# butter.net
KiCad netlist of a schematic drawn in EAGLE
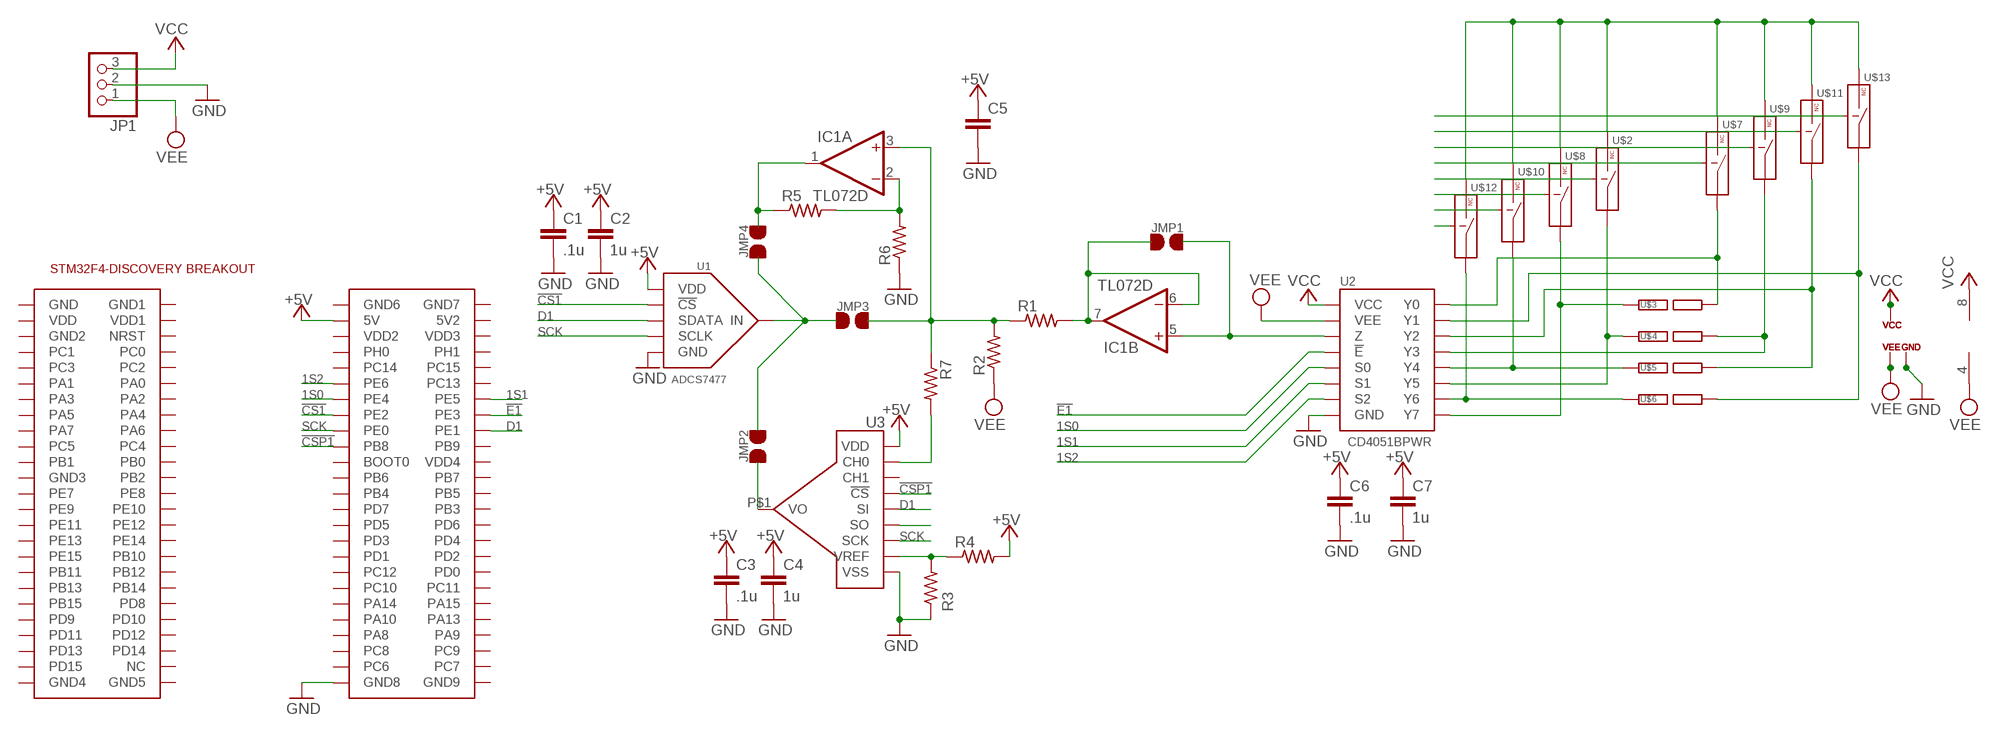
[diagram p0: schematic, sheet 1]

(export (version "E")
  (design (tool "Eeschema 10.0.6"))
  (components
    (comp (ref "C1")
      (value ".1u")
      (footprint "eagle-import:C0805")
      (libsource (lib "eagle-import") (part "C-EUC0805"))
    )
    (comp (ref "C2")
      (value "1u")
      (footprint "eagle-import:C0805")
      (libsource (lib "eagle-import") (part "C-EUC0805"))
    )
    (comp (ref "C3")
      (value ".1u")
      (footprint "eagle-import:C0805")
      (libsource (lib "eagle-import") (part "C-EUC0805"))
    )
    (comp (ref "C4")
      (value "1u")
      (footprint "eagle-import:C0805")
      (libsource (lib "eagle-import") (part "C-EUC0805"))
    )
    (comp (ref "C5")
      (value "C-EUC0805")
      (footprint "eagle-import:C0805")
      (libsource (lib "eagle-import") (part "C-EUC0805"))
    )
    (comp (ref "C6")
      (value ".1u")
      (footprint "eagle-import:C0805")
      (libsource (lib "eagle-import") (part "C-EUC0805"))
    )
    (comp (ref "C7")
      (value "1u")
      (footprint "eagle-import:C0805")
      (libsource (lib "eagle-import") (part "C-EUC0805"))
    )
    (comp (ref "IC1")
      (value "TL072D")
      (footprint "eagle-import:SO08")
      (libsource (lib "eagle-import") (part "TL072D"))
    )
    (comp (ref "JMP1")
      (value "JMP")
      (footprint "eagle-import:JMP")
      (libsource (lib "eagle-import") (part "JMP"))
    )
    (comp (ref "JMP2")
      (value "JMP")
      (footprint "eagle-import:JMP")
      (libsource (lib "eagle-import") (part "JMP"))
    )
    (comp (ref "JMP3")
      (value "JMP")
      (footprint "eagle-import:JMP")
      (libsource (lib "eagle-import") (part "JMP"))
    )
    (comp (ref "JMP4")
      (value "JMP")
      (footprint "eagle-import:JMP")
      (libsource (lib "eagle-import") (part "JMP"))
    )
    (comp (ref "JP1")
      (value "PINHD-1X3")
      (footprint "eagle-import:1X03")
      (libsource (lib "eagle-import") (part "PINHD-1X3"))
    )
    (comp (ref "R1")
      (value "R-US_R0603")
      (footprint "eagle-import:R0603")
      (libsource (lib "eagle-import") (part "R-US_R0603"))
    )
    (comp (ref "R2")
      (value "R-US_R0603")
      (footprint "eagle-import:R0603")
      (libsource (lib "eagle-import") (part "R-US_R0603"))
    )
    (comp (ref "R3")
      (value "R-US_R0603")
      (footprint "eagle-import:R0603")
      (libsource (lib "eagle-import") (part "R-US_R0603"))
    )
    (comp (ref "R4")
      (value "R-US_R0603")
      (footprint "eagle-import:R0603")
      (libsource (lib "eagle-import") (part "R-US_R0603"))
    )
    (comp (ref "R5")
      (value "R-US_R0603")
      (footprint "eagle-import:R0603")
      (libsource (lib "eagle-import") (part "R-US_R0603"))
    )
    (comp (ref "R6")
      (value "R-US_R0603")
      (footprint "eagle-import:R0603")
      (libsource (lib "eagle-import") (part "R-US_R0603"))
    )
    (comp (ref "R7")
      (value "R-US_R0603")
      (footprint "eagle-import:R0603")
      (libsource (lib "eagle-import") (part "R-US_R0603"))
    )
    (comp (ref "U$1")
      (value "STM32F4-DISCOVERY")
      (footprint "eagle-import:STM32F4-DISCOVERY")
      (libsource (lib "eagle-import") (part "STM32F4-DISCOVERY"))
    )
    (comp (ref "U$2")
      (value "DG467")
      (footprint "eagle-import:TSSOP-6")
      (libsource (lib "eagle-import") (part "DG467"))
    )
    (comp (ref "U$3")
      (value "RAILSEP")
      (footprint "eagle-import:RAIL")
      (libsource (lib "eagle-import") (part "RAILSEP"))
    )
    (comp (ref "U$4")
      (value "RAILSEP")
      (footprint "eagle-import:RAIL")
      (libsource (lib "eagle-import") (part "RAILSEP"))
    )
    (comp (ref "U$5")
      (value "RAILSEP")
      (footprint "eagle-import:RAIL")
      (libsource (lib "eagle-import") (part "RAILSEP"))
    )
    (comp (ref "U$6")
      (value "RAILSEP")
      (footprint "eagle-import:RAIL")
      (libsource (lib "eagle-import") (part "RAILSEP"))
    )
    (comp (ref "U$7")
      (value "DG467")
      (footprint "eagle-import:TSSOP-6")
      (libsource (lib "eagle-import") (part "DG467"))
    )
    (comp (ref "U$8")
      (value "DG467")
      (footprint "eagle-import:TSSOP-6")
      (libsource (lib "eagle-import") (part "DG467"))
    )
    (comp (ref "U$9")
      (value "DG467")
      (footprint "eagle-import:TSSOP-6")
      (libsource (lib "eagle-import") (part "DG467"))
    )
    (comp (ref "U$10")
      (value "DG467")
      (footprint "eagle-import:TSSOP-6")
      (libsource (lib "eagle-import") (part "DG467"))
    )
    (comp (ref "U$11")
      (value "DG467")
      (footprint "eagle-import:TSSOP-6")
      (libsource (lib "eagle-import") (part "DG467"))
    )
    (comp (ref "U$12")
      (value "DG467")
      (footprint "eagle-import:TSSOP-6")
      (libsource (lib "eagle-import") (part "DG467"))
    )
    (comp (ref "U$13")
      (value "DG467")
      (footprint "eagle-import:TSSOP-6")
      (libsource (lib "eagle-import") (part "DG467"))
    )
    (comp (ref "U1")
      (value "ADCS7477")
      (footprint "eagle-import:SOT-23-6")
      (libsource (lib "eagle-import") (part "ADCS7477"))
    )
    (comp (ref "U2")
      (value "CD4051BPWR")
      (footprint "eagle-import:TSSOP-16")
      (libsource (lib "eagle-import") (part "CD4051BPWR"))
    )
    (comp (ref "U3")
      (value "MCP6S93")
      (footprint "eagle-import:MSOP-10")
      (libsource (lib "eagle-import") (part "MCP6S93"))
    )
  )
  (nets
    (net (code "1") (name "+5V") (class "Default")
      (node (ref "C1") (pin "1") (pinfunction "1_1") (pintype "passive"))
      (node (ref "C2") (pin "1") (pinfunction "1_1") (pintype "passive"))
      (node (ref "C3") (pin "1") (pinfunction "1_1") (pintype "passive"))
      (node (ref "C4") (pin "1") (pinfunction "1_1") (pintype "passive"))
      (node (ref "C5") (pin "1") (pinfunction "1_1") (pintype "passive"))
      (node (ref "C6") (pin "1") (pinfunction "1_1") (pintype "passive"))
      (node (ref "C7") (pin "1") (pinfunction "1_1") (pintype "passive"))
      (node (ref "R4") (pin "2") (pinfunction "2_2") (pintype "passive"))
      (node (ref "U$1") (pin "P$53") (pinfunction "5V_P$53") (pintype "bidirectional"))
      (node (ref "U1") (pin "P$1") (pinfunction "VDD_P$1") (pintype "bidirectional"))
      (node (ref "U3") (pin "P$10") (pinfunction "VDD_P$10") (pintype "bidirectional"))
    )
    (net (code "2") (name "/1S0") (class "Default")
      (node (ref "U$1") (pin "P$63") (pinfunction "PE4_P$63") (pintype "bidirectional"))
      (node (ref "U2") (pin "P$11") (pinfunction "S0_P$11") (pintype "bidirectional"))
    )
    (net (code "3") (name "/1S1") (class "Default")
      (node (ref "U$1") (pin "P$64") (pinfunction "PE5_P$64") (pintype "bidirectional"))
      (node (ref "U2") (pin "P$10") (pinfunction "S1_P$10") (pintype "bidirectional"))
    )
    (net (code "4") (name "/1S2") (class "Default")
      (node (ref "U$1") (pin "P$61") (pinfunction "PE6_P$61") (pintype "bidirectional"))
      (node (ref "U2") (pin "P$9") (pinfunction "S2_P$9") (pintype "bidirectional"))
    )
    (net (code "5") (name "/D1") (class "Default")
      (node (ref "U$1") (pin "P$68") (pinfunction "PE1_P$68") (pintype "bidirectional"))
      (node (ref "U1") (pin "P$5") (pinfunction "SDATA_P$5") (pintype "bidirectional"))
      (node (ref "U3") (pin "P$7") (pinfunction "SI_P$7") (pintype "bidirectional"))
    )
    (net (code "6") (name "/SCK") (class "Default")
      (node (ref "U$1") (pin "P$67") (pinfunction "PE0_P$67") (pintype "bidirectional"))
      (node (ref "U1") (pin "P$4") (pinfunction "SCLK_P$4") (pintype "bidirectional"))
      (node (ref "U3") (pin "P$9") (pinfunction "SCK_P$9") (pintype "bidirectional"))
    )
    (net (code "7") (name "/~{CS1}") (class "Default")
      (node (ref "U$1") (pin "P$65") (pinfunction "PE2_P$65") (pintype "bidirectional"))
      (node (ref "U1") (pin "P$6") (pinfunction "~{CS}_P$6") (pintype "bidirectional"))
    )
    (net (code "8") (name "/~{CSP1}") (class "Default")
      (node (ref "U$1") (pin "P$69") (pinfunction "PB8_P$69") (pintype "bidirectional"))
      (node (ref "U3") (pin "P$6") (pinfunction "~{CS}_P$6") (pintype "bidirectional"))
    )
    (net (code "9") (name "/~{E1}") (class "Default")
      (node (ref "U$1") (pin "P$66") (pinfunction "PE3_P$66") (pintype "bidirectional"))
      (node (ref "U2") (pin "P$6") (pinfunction "~{E}_P$6") (pintype "bidirectional"))
    )
    (net (code "10") (name "GND") (class "Default")
      (node (ref "C1") (pin "2") (pinfunction "2_2") (pintype "passive"))
      (node (ref "C2") (pin "2") (pinfunction "2_2") (pintype "passive"))
      (node (ref "C3") (pin "2") (pinfunction "2_2") (pintype "passive"))
      (node (ref "C4") (pin "2") (pinfunction "2_2") (pintype "passive"))
      (node (ref "C5") (pin "2") (pinfunction "2_2") (pintype "passive"))
      (node (ref "C6") (pin "2") (pinfunction "2_2") (pintype "passive"))
      (node (ref "C7") (pin "2") (pinfunction "2_2") (pintype "passive"))
      (node (ref "JP1") (pin "2") (pinfunction "2_2") (pintype "passive"))
      (node (ref "R3") (pin "1") (pinfunction "1_1") (pintype "passive"))
      (node (ref "R6") (pin "1") (pinfunction "1_1") (pintype "passive"))
      (node (ref "U$1") (pin "P$99") (pinfunction "GND8_P$99") (pintype "bidirectional"))
      (node (ref "U$10") (pin "P$4") (pinfunction "GND_P$4") (pintype "bidirectional"))
      (node (ref "U$11") (pin "P$4") (pinfunction "GND_P$4") (pintype "bidirectional"))
      (node (ref "U$12") (pin "P$4") (pinfunction "GND_P$4") (pintype "bidirectional"))
      (node (ref "U$13") (pin "P$4") (pinfunction "GND_P$4") (pintype "bidirectional"))
      (node (ref "U$2") (pin "P$4") (pinfunction "GND_P$4") (pintype "bidirectional"))
      (node (ref "U$7") (pin "P$4") (pinfunction "GND_P$4") (pintype "bidirectional"))
      (node (ref "U$8") (pin "P$4") (pinfunction "GND_P$4") (pintype "bidirectional"))
      (node (ref "U$9") (pin "P$4") (pinfunction "GND_P$4") (pintype "bidirectional"))
      (node (ref "U1") (pin "P$2") (pinfunction "GND_P$2") (pintype "bidirectional"))
      (node (ref "U2") (pin "P$8") (pinfunction "GND_P$8") (pintype "bidirectional"))
      (node (ref "U3") (pin "P$5") (pinfunction "VSS_P$5") (pintype "bidirectional"))
    )
    (net (code "11") (name "Net-(IC1A-+IN)") (class "Default")
      (node (ref "IC1") (pin "3") (pinfunction "+IN_3") (pintype "input"))
      (node (ref "JMP3") (pin "P$2") (pinfunction "P$2_P$2") (pintype "bidirectional"))
      (node (ref "R1") (pin "1") (pinfunction "1_1") (pintype "passive"))
      (node (ref "R2") (pin "2") (pinfunction "2_2") (pintype "passive"))
      (node (ref "R7") (pin "1") (pinfunction "1_1") (pintype "passive"))
    )
    (net (code "12") (name "Net-(IC1A--IN)") (class "Default")
      (node (ref "IC1") (pin "2") (pinfunction "-IN_2") (pintype "input"))
      (node (ref "R5") (pin "2") (pinfunction "2_2") (pintype "passive"))
      (node (ref "R6") (pin "2") (pinfunction "2_2") (pintype "passive"))
    )
    (net (code "13") (name "Net-(IC1A-OUT)") (class "Default")
      (node (ref "IC1") (pin "1") (pinfunction "OUT_1") (pintype "output"))
      (node (ref "JMP4") (pin "P$2") (pinfunction "P$2_P$2") (pintype "bidirectional"))
      (node (ref "R5") (pin "1") (pinfunction "1_1") (pintype "passive"))
    )
    (net (code "14") (name "Net-(IC1B-+IN)") (class "Default")
      (node (ref "IC1") (pin "5") (pinfunction "+IN_5") (pintype "input"))
      (node (ref "JMP1") (pin "P$2") (pinfunction "P$2_P$2") (pintype "bidirectional"))
      (node (ref "U2") (pin "P$3") (pinfunction "Z_P$3") (pintype "bidirectional"))
    )
    (net (code "15") (name "Net-(IC1B--IN)") (class "Default")
      (node (ref "IC1") (pin "6") (pinfunction "-IN_6") (pintype "input"))
      (node (ref "IC1") (pin "7") (pinfunction "OUT_7") (pintype "output"))
      (node (ref "JMP1") (pin "P$1") (pinfunction "P$1_P$1") (pintype "bidirectional"))
      (node (ref "R1") (pin "2") (pinfunction "2_2") (pintype "passive"))
    )
    (net (code "16") (name "Net-(U$2A-COM)") (class "Default")
      (node (ref "U$2") (pin "P$6") (pinfunction "COM_P$6") (pintype "bidirectional"))
      (node (ref "U$4") (pin "P$L") (pinfunction "L_P$L") (pintype "bidirectional"))
      (node (ref "U2") (pin "P$5") (pinfunction "Y5_P$5") (pintype "bidirectional"))
    )
    (net (code "17") (name "Net-(U$3-L)") (class "Default")
      (node (ref "U$3") (pin "P$L") (pinfunction "L_P$L") (pintype "bidirectional"))
      (node (ref "U$8") (pin "P$6") (pinfunction "COM_P$6") (pintype "bidirectional"))
      (node (ref "U2") (pin "P$4") (pinfunction "Y7_P$4") (pintype "bidirectional"))
    )
    (net (code "18") (name "Net-(U$3-R)") (class "Default")
      (node (ref "U$3") (pin "P$R") (pinfunction "R_P$R") (pintype "bidirectional"))
      (node (ref "U$7") (pin "P$6") (pinfunction "COM_P$6") (pintype "bidirectional"))
      (node (ref "U2") (pin "P$13") (pinfunction "Y0_P$13") (pintype "bidirectional"))
    )
    (net (code "19") (name "Net-(U$4-R)") (class "Default")
      (node (ref "U$4") (pin "P$R") (pinfunction "R_P$R") (pintype "bidirectional"))
      (node (ref "U$9") (pin "P$6") (pinfunction "COM_P$6") (pintype "bidirectional"))
      (node (ref "U2") (pin "P$12") (pinfunction "Y3_P$12") (pintype "bidirectional"))
    )
    (net (code "20") (name "Net-(U$10A-COM)") (class "Default")
      (node (ref "U$10") (pin "P$6") (pinfunction "COM_P$6") (pintype "bidirectional"))
      (node (ref "U$5") (pin "P$L") (pinfunction "L_P$L") (pintype "bidirectional"))
      (node (ref "U2") (pin "P$1") (pinfunction "Y4_P$1") (pintype "bidirectional"))
    )
    (net (code "21") (name "Net-(U$10A-IN)") (class "Default")
      (node (ref "U$10") (pin "P$1") (pinfunction "IN_P$1") (pintype "bidirectional"))
      (node (ref "U$11") (pin "P$1") (pinfunction "IN_P$1") (pintype "bidirectional"))
      (node (ref "U$12") (pin "P$1") (pinfunction "IN_P$1") (pintype "bidirectional"))
      (node (ref "U$13") (pin "P$1") (pinfunction "IN_P$1") (pintype "bidirectional"))
      (node (ref "U$2") (pin "P$1") (pinfunction "IN_P$1") (pintype "bidirectional"))
      (node (ref "U$7") (pin "P$1") (pinfunction "IN_P$1") (pintype "bidirectional"))
      (node (ref "U$8") (pin "P$1") (pinfunction "IN_P$1") (pintype "bidirectional"))
      (node (ref "U$9") (pin "P$1") (pinfunction "IN_P$1") (pintype "bidirectional"))
    )
    (net (code "22") (name "Net-(U$11A-COM)") (class "Default")
      (node (ref "U$11") (pin "P$6") (pinfunction "COM_P$6") (pintype "bidirectional"))
      (node (ref "U$5") (pin "P$R") (pinfunction "R_P$R") (pintype "bidirectional"))
      (node (ref "U2") (pin "P$15") (pinfunction "Y2_P$15") (pintype "bidirectional"))
    )
    (net (code "23") (name "Net-(U$12A-COM)") (class "Default")
      (node (ref "U$12") (pin "P$6") (pinfunction "COM_P$6") (pintype "bidirectional"))
      (node (ref "U$6") (pin "P$L") (pinfunction "L_P$L") (pintype "bidirectional"))
      (node (ref "U2") (pin "P$2") (pinfunction "Y6_P$2") (pintype "bidirectional"))
    )
    (net (code "24") (name "Net-(U$13A-COM)") (class "Default")
      (node (ref "U$13") (pin "P$6") (pinfunction "COM_P$6") (pintype "bidirectional"))
      (node (ref "U$6") (pin "P$R") (pinfunction "R_P$R") (pintype "bidirectional"))
      (node (ref "U2") (pin "P$14") (pinfunction "Y1_P$14") (pintype "bidirectional"))
    )
    (net (code "25") (name "Net-(U1-IN)") (class "Default")
      (node (ref "JMP2") (pin "P$2") (pinfunction "P$2_P$2") (pintype "bidirectional"))
      (node (ref "JMP3") (pin "P$1") (pinfunction "P$1_P$1") (pintype "bidirectional"))
      (node (ref "JMP4") (pin "P$1") (pinfunction "P$1_P$1") (pintype "bidirectional"))
      (node (ref "U1") (pin "P$3") (pinfunction "IN_P$3") (pintype "bidirectional"))
    )
    (net (code "26") (name "Net-(U3-CH0)") (class "Default")
      (node (ref "R7") (pin "2") (pinfunction "2_2") (pintype "passive"))
      (node (ref "U3") (pin "P$2") (pinfunction "CH0_P$2") (pintype "bidirectional"))
    )
    (net (code "27") (name "Net-(U3-VO)") (class "Default")
      (node (ref "JMP2") (pin "P$1") (pinfunction "P$1_P$1") (pintype "bidirectional"))
      (node (ref "U3") (pin "P$1") (pinfunction "VO_P$1") (pintype "bidirectional"))
    )
    (net (code "28") (name "Net-(U3-VREF)") (class "Default")
      (node (ref "R3") (pin "2") (pinfunction "2_2") (pintype "passive"))
      (node (ref "R4") (pin "1") (pinfunction "1_1") (pintype "passive"))
      (node (ref "U3") (pin "P$4") (pinfunction "VREF_P$4") (pintype "bidirectional"))
    )
    (net (code "29") (name "VCC") (class "Default")
      (node (ref "IC1") (pin "8") (pinfunction "V+_8") (pintype "power_in"))
      (node (ref "JP1") (pin "3") (pinfunction "3_3") (pintype "passive"))
      (node (ref "U$10") (pin "P$5") (pinfunction "VCC_P$5") (pintype "bidirectional"))
      (node (ref "U$11") (pin "P$5") (pinfunction "VCC_P$5") (pintype "bidirectional"))
      (node (ref "U$12") (pin "P$5") (pinfunction "VCC_P$5") (pintype "bidirectional"))
      (node (ref "U$13") (pin "P$5") (pinfunction "VCC_P$5") (pintype "bidirectional"))
      (node (ref "U$2") (pin "P$5") (pinfunction "VCC_P$5") (pintype "bidirectional"))
      (node (ref "U$7") (pin "P$5") (pinfunction "VCC_P$5") (pintype "bidirectional"))
      (node (ref "U$8") (pin "P$5") (pinfunction "VCC_P$5") (pintype "bidirectional"))
      (node (ref "U$9") (pin "P$5") (pinfunction "VCC_P$5") (pintype "bidirectional"))
      (node (ref "U2") (pin "P$16") (pinfunction "VCC_P$16") (pintype "bidirectional"))
    )
    (net (code "30") (name "VEE") (class "Default")
      (node (ref "IC1") (pin "4") (pinfunction "V-_4") (pintype "power_in"))
      (node (ref "JP1") (pin "1") (pinfunction "1_1") (pintype "passive"))
      (node (ref "R2") (pin "1") (pinfunction "1_1") (pintype "passive"))
      (node (ref "U$10") (pin "P$2") (pinfunction "VEE_P$2") (pintype "bidirectional"))
      (node (ref "U$11") (pin "P$2") (pinfunction "VEE_P$2") (pintype "bidirectional"))
      (node (ref "U$12") (pin "P$2") (pinfunction "VEE_P$2") (pintype "bidirectional"))
      (node (ref "U$13") (pin "P$2") (pinfunction "VEE_P$2") (pintype "bidirectional"))
      (node (ref "U$2") (pin "P$2") (pinfunction "VEE_P$2") (pintype "bidirectional"))
      (node (ref "U$7") (pin "P$2") (pinfunction "VEE_P$2") (pintype "bidirectional"))
      (node (ref "U$8") (pin "P$2") (pinfunction "VEE_P$2") (pintype "bidirectional"))
      (node (ref "U$9") (pin "P$2") (pinfunction "VEE_P$2") (pintype "bidirectional"))
      (node (ref "U2") (pin "P$7") (pinfunction "VEE_P$7") (pintype "bidirectional"))
    )
    (net (code "31") (name "unconnected-(U$1-5V2-PadP$54)") (class "Default")
      (node (ref "U$1") (pin "P$54") (pinfunction "5V2_P$54") (pintype "bidirectional"))
    )
    (net (code "32") (name "unconnected-(U$1-BOOT0-PadP$71)") (class "Default")
      (node (ref "U$1") (pin "P$71") (pinfunction "BOOT0_P$71") (pintype "bidirectional"))
    )
    (net (code "33") (name "unconnected-(U$1-GND-PadP$1)") (class "Default")
      (node (ref "U$1") (pin "P$1") (pinfunction "GND_P$1") (pintype "bidirectional"))
    )
    (net (code "34") (name "unconnected-(U$1-GND1-PadP$2)") (class "Default")
      (node (ref "U$1") (pin "P$2") (pinfunction "GND1_P$2") (pintype "bidirectional"))
    )
    (net (code "35") (name "unconnected-(U$1-GND2-PadP$5)") (class "Default")
      (node (ref "U$1") (pin "P$5") (pinfunction "GND2_P$5") (pintype "bidirectional"))
    )
    (net (code "36") (name "unconnected-(U$1-GND3-PadP$23)") (class "Default")
      (node (ref "U$1") (pin "P$23") (pinfunction "GND3_P$23") (pintype "bidirectional"))
    )
    (net (code "37") (name "unconnected-(U$1-GND4-PadP$49)") (class "Default")
      (node (ref "U$1") (pin "P$49") (pinfunction "GND4_P$49") (pintype "bidirectional"))
    )
    (net (code "38") (name "unconnected-(U$1-GND5-PadP$50)") (class "Default")
      (node (ref "U$1") (pin "P$50") (pinfunction "GND5_P$50") (pintype "bidirectional"))
    )
    (net (code "39") (name "unconnected-(U$1-GND6-PadP$51)") (class "Default")
      (node (ref "U$1") (pin "P$51") (pinfunction "GND6_P$51") (pintype "bidirectional"))
    )
    (net (code "40") (name "unconnected-(U$1-GND7-PadP$52)") (class "Default")
      (node (ref "U$1") (pin "P$52") (pinfunction "GND7_P$52") (pintype "bidirectional"))
    )
    (net (code "41") (name "unconnected-(U$1-GND9-PadP$100)") (class "Default")
      (node (ref "U$1") (pin "P$100") (pinfunction "GND9_P$100") (pintype "bidirectional"))
    )
    (net (code "42") (name "unconnected-(U$1-NC-PadP$48)") (class "Default")
      (node (ref "U$1") (pin "P$48") (pinfunction "NC_P$48") (pintype "bidirectional"))
    )
    (net (code "43") (name "unconnected-(U$1-NRST-PadP$6)") (class "Default")
      (node (ref "U$1") (pin "P$6") (pinfunction "NRST_P$6") (pintype "bidirectional"))
    )
    (net (code "44") (name "unconnected-(U$1-PA0-PadP$12)") (class "Default")
      (node (ref "U$1") (pin "P$12") (pinfunction "PA0_P$12") (pintype "bidirectional"))
    )
    (net (code "45") (name "unconnected-(U$1-PA1-PadP$11)") (class "Default")
      (node (ref "U$1") (pin "P$11") (pinfunction "PA1_P$11") (pintype "bidirectional"))
    )
    (net (code "46") (name "unconnected-(U$1-PA2-PadP$14)") (class "Default")
      (node (ref "U$1") (pin "P$14") (pinfunction "PA2_P$14") (pintype "bidirectional"))
    )
    (net (code "47") (name "unconnected-(U$1-PA3-PadP$13)") (class "Default")
      (node (ref "U$1") (pin "P$13") (pinfunction "PA3_P$13") (pintype "bidirectional"))
    )
    (net (code "48") (name "unconnected-(U$1-PA4-PadP$16)") (class "Default")
      (node (ref "U$1") (pin "P$16") (pinfunction "PA4_P$16") (pintype "bidirectional"))
    )
    (net (code "49") (name "unconnected-(U$1-PA5-PadP$15)") (class "Default")
      (node (ref "U$1") (pin "P$15") (pinfunction "PA5_P$15") (pintype "bidirectional"))
    )
    (net (code "50") (name "unconnected-(U$1-PA6-PadP$18)") (class "Default")
      (node (ref "U$1") (pin "P$18") (pinfunction "PA6_P$18") (pintype "bidirectional"))
    )
    (net (code "51") (name "unconnected-(U$1-PA7-PadP$17)") (class "Default")
      (node (ref "U$1") (pin "P$17") (pinfunction "PA7_P$17") (pintype "bidirectional"))
    )
    (net (code "52") (name "unconnected-(U$1-PA8-PadP$93)") (class "Default")
      (node (ref "U$1") (pin "P$93") (pinfunction "PA8_P$93") (pintype "bidirectional"))
    )
    (net (code "53") (name "unconnected-(U$1-PA9-PadP$94)") (class "Default")
      (node (ref "U$1") (pin "P$94") (pinfunction "PA9_P$94") (pintype "bidirectional"))
    )
    (net (code "54") (name "unconnected-(U$1-PA10-PadP$91)") (class "Default")
      (node (ref "U$1") (pin "P$91") (pinfunction "PA10_P$91") (pintype "bidirectional"))
    )
    (net (code "55") (name "unconnected-(U$1-PA13-PadP$92)") (class "Default")
      (node (ref "U$1") (pin "P$92") (pinfunction "PA13_P$92") (pintype "bidirectional"))
    )
    (net (code "56") (name "unconnected-(U$1-PA14-PadP$89)") (class "Default")
      (node (ref "U$1") (pin "P$89") (pinfunction "PA14_P$89") (pintype "bidirectional"))
    )
    (net (code "57") (name "unconnected-(U$1-PA15-PadP$90)") (class "Default")
      (node (ref "U$1") (pin "P$90") (pinfunction "PA15_P$90") (pintype "bidirectional"))
    )
    (net (code "58") (name "unconnected-(U$1-PB0-PadP$22)") (class "Default")
      (node (ref "U$1") (pin "P$22") (pinfunction "PB0_P$22") (pintype "bidirectional"))
    )
    (net (code "59") (name "unconnected-(U$1-PB1-PadP$21)") (class "Default")
      (node (ref "U$1") (pin "P$21") (pinfunction "PB1_P$21") (pintype "bidirectional"))
    )
    (net (code "60") (name "unconnected-(U$1-PB2-PadP$24)") (class "Default")
      (node (ref "U$1") (pin "P$24") (pinfunction "PB2_P$24") (pintype "bidirectional"))
    )
    (net (code "61") (name "unconnected-(U$1-PB3-PadP$78)") (class "Default")
      (node (ref "U$1") (pin "P$78") (pinfunction "PB3_P$78") (pintype "bidirectional"))
    )
    (net (code "62") (name "unconnected-(U$1-PB4-PadP$75)") (class "Default")
      (node (ref "U$1") (pin "P$75") (pinfunction "PB4_P$75") (pintype "bidirectional"))
    )
    (net (code "63") (name "unconnected-(U$1-PB5-PadP$76)") (class "Default")
      (node (ref "U$1") (pin "P$76") (pinfunction "PB5_P$76") (pintype "bidirectional"))
    )
    (net (code "64") (name "unconnected-(U$1-PB6-PadP$73)") (class "Default")
      (node (ref "U$1") (pin "P$73") (pinfunction "PB6_P$73") (pintype "bidirectional"))
    )
    (net (code "65") (name "unconnected-(U$1-PB7-PadP$74)") (class "Default")
      (node (ref "U$1") (pin "P$74") (pinfunction "PB7_P$74") (pintype "bidirectional"))
    )
    (net (code "66") (name "unconnected-(U$1-PB9-PadP$70)") (class "Default")
      (node (ref "U$1") (pin "P$70") (pinfunction "PB9_P$70") (pintype "bidirectional"))
    )
    (net (code "67") (name "unconnected-(U$1-PB10-PadP$34)") (class "Default")
      (node (ref "U$1") (pin "P$34") (pinfunction "PB10_P$34") (pintype "bidirectional"))
    )
    (net (code "68") (name "unconnected-(U$1-PB11-PadP$35)") (class "Default")
      (node (ref "U$1") (pin "P$35") (pinfunction "PB11_P$35") (pintype "bidirectional"))
    )
    (net (code "69") (name "unconnected-(U$1-PB12-PadP$36)") (class "Default")
      (node (ref "U$1") (pin "P$36") (pinfunction "PB12_P$36") (pintype "bidirectional"))
    )
    (net (code "70") (name "unconnected-(U$1-PB13-PadP$37)") (class "Default")
      (node (ref "U$1") (pin "P$37") (pinfunction "PB13_P$37") (pintype "bidirectional"))
    )
    (net (code "71") (name "unconnected-(U$1-PB14-PadP$38)") (class "Default")
      (node (ref "U$1") (pin "P$38") (pinfunction "PB14_P$38") (pintype "bidirectional"))
    )
    (net (code "72") (name "unconnected-(U$1-PB15-PadP$39)") (class "Default")
      (node (ref "U$1") (pin "P$39") (pinfunction "PB15_P$39") (pintype "bidirectional"))
    )
    (net (code "73") (name "unconnected-(U$1-PC0-PadP$8)") (class "Default")
      (node (ref "U$1") (pin "P$8") (pinfunction "PC0_P$8") (pintype "bidirectional"))
    )
    (net (code "74") (name "unconnected-(U$1-PC1-PadP$7)") (class "Default")
      (node (ref "U$1") (pin "P$7") (pinfunction "PC1_P$7") (pintype "bidirectional"))
    )
    (net (code "75") (name "unconnected-(U$1-PC2-PadP$10)") (class "Default")
      (node (ref "U$1") (pin "P$10") (pinfunction "PC2_P$10") (pintype "bidirectional"))
    )
    (net (code "76") (name "unconnected-(U$1-PC3-PadP$9)") (class "Default")
      (node (ref "U$1") (pin "P$9") (pinfunction "PC3_P$9") (pintype "bidirectional"))
    )
    (net (code "77") (name "unconnected-(U$1-PC4-PadP$20)") (class "Default")
      (node (ref "U$1") (pin "P$20") (pinfunction "PC4_P$20") (pintype "bidirectional"))
    )
    (net (code "78") (name "unconnected-(U$1-PC5-PadP$19)") (class "Default")
      (node (ref "U$1") (pin "P$19") (pinfunction "PC5_P$19") (pintype "bidirectional"))
    )
    (net (code "79") (name "unconnected-(U$1-PC6-PadP$97)") (class "Default")
      (node (ref "U$1") (pin "P$97") (pinfunction "PC6_P$97") (pintype "bidirectional"))
    )
    (net (code "80") (name "unconnected-(U$1-PC7-PadP$98)") (class "Default")
      (node (ref "U$1") (pin "P$98") (pinfunction "PC7_P$98") (pintype "bidirectional"))
    )
    (net (code "81") (name "unconnected-(U$1-PC8-PadP$95)") (class "Default")
      (node (ref "U$1") (pin "P$95") (pinfunction "PC8_P$95") (pintype "bidirectional"))
    )
    (net (code "82") (name "unconnected-(U$1-PC9-PadP$96)") (class "Default")
      (node (ref "U$1") (pin "P$96") (pinfunction "PC9_P$96") (pintype "bidirectional"))
    )
    (net (code "83") (name "unconnected-(U$1-PC10-PadP$87)") (class "Default")
      (node (ref "U$1") (pin "P$87") (pinfunction "PC10_P$87") (pintype "bidirectional"))
    )
    (net (code "84") (name "unconnected-(U$1-PC11-PadP$88)") (class "Default")
      (node (ref "U$1") (pin "P$88") (pinfunction "PC11_P$88") (pintype "bidirectional"))
    )
    (net (code "85") (name "unconnected-(U$1-PC12-PadP$85)") (class "Default")
      (node (ref "U$1") (pin "P$85") (pinfunction "PC12_P$85") (pintype "bidirectional"))
    )
    (net (code "86") (name "unconnected-(U$1-PC13-PadP$62)") (class "Default")
      (node (ref "U$1") (pin "P$62") (pinfunction "PC13_P$62") (pintype "bidirectional"))
    )
    (net (code "87") (name "unconnected-(U$1-PC14-PadP$59)") (class "Default")
      (node (ref "U$1") (pin "P$59") (pinfunction "PC14_P$59") (pintype "bidirectional"))
    )
    (net (code "88") (name "unconnected-(U$1-PC15-PadP$60)") (class "Default")
      (node (ref "U$1") (pin "P$60") (pinfunction "PC15_P$60") (pintype "bidirectional"))
    )
    (net (code "89") (name "unconnected-(U$1-PD0-PadP$86)") (class "Default")
      (node (ref "U$1") (pin "P$86") (pinfunction "PD0_P$86") (pintype "bidirectional"))
    )
    (net (code "90") (name "unconnected-(U$1-PD1-PadP$83)") (class "Default")
      (node (ref "U$1") (pin "P$83") (pinfunction "PD1_P$83") (pintype "bidirectional"))
    )
    (net (code "91") (name "unconnected-(U$1-PD2-PadP$84)") (class "Default")
      (node (ref "U$1") (pin "P$84") (pinfunction "PD2_P$84") (pintype "bidirectional"))
    )
    (net (code "92") (name "unconnected-(U$1-PD3-PadP$81)") (class "Default")
      (node (ref "U$1") (pin "P$81") (pinfunction "PD3_P$81") (pintype "bidirectional"))
    )
    (net (code "93") (name "unconnected-(U$1-PD4-PadP$82)") (class "Default")
      (node (ref "U$1") (pin "P$82") (pinfunction "PD4_P$82") (pintype "bidirectional"))
    )
    (net (code "94") (name "unconnected-(U$1-PD5-PadP$79)") (class "Default")
      (node (ref "U$1") (pin "P$79") (pinfunction "PD5_P$79") (pintype "bidirectional"))
    )
    (net (code "95") (name "unconnected-(U$1-PD6-PadP$80)") (class "Default")
      (node (ref "U$1") (pin "P$80") (pinfunction "PD6_P$80") (pintype "bidirectional"))
    )
    (net (code "96") (name "unconnected-(U$1-PD7-PadP$77)") (class "Default")
      (node (ref "U$1") (pin "P$77") (pinfunction "PD7_P$77") (pintype "bidirectional"))
    )
    (net (code "97") (name "unconnected-(U$1-PD8-PadP$40)") (class "Default")
      (node (ref "U$1") (pin "P$40") (pinfunction "PD8_P$40") (pintype "bidirectional"))
    )
    (net (code "98") (name "unconnected-(U$1-PD9-PadP$41)") (class "Default")
      (node (ref "U$1") (pin "P$41") (pinfunction "PD9_P$41") (pintype "bidirectional"))
    )
    (net (code "99") (name "unconnected-(U$1-PD10-PadP$42)") (class "Default")
      (node (ref "U$1") (pin "P$42") (pinfunction "PD10_P$42") (pintype "bidirectional"))
    )
    (net (code "100") (name "unconnected-(U$1-PD11-PadP$43)") (class "Default")
      (node (ref "U$1") (pin "P$43") (pinfunction "PD11_P$43") (pintype "bidirectional"))
    )
    (net (code "101") (name "unconnected-(U$1-PD12-PadP$44)") (class "Default")
      (node (ref "U$1") (pin "P$44") (pinfunction "PD12_P$44") (pintype "bidirectional"))
    )
    (net (code "102") (name "unconnected-(U$1-PD13-PadP$45)") (class "Default")
      (node (ref "U$1") (pin "P$45") (pinfunction "PD13_P$45") (pintype "bidirectional"))
    )
    (net (code "103") (name "unconnected-(U$1-PD14-PadP$46)") (class "Default")
      (node (ref "U$1") (pin "P$46") (pinfunction "PD14_P$46") (pintype "bidirectional"))
    )
    (net (code "104") (name "unconnected-(U$1-PD15-PadP$47)") (class "Default")
      (node (ref "U$1") (pin "P$47") (pinfunction "PD15_P$47") (pintype "bidirectional"))
    )
    (net (code "105") (name "unconnected-(U$1-PE7-PadP$25)") (class "Default")
      (node (ref "U$1") (pin "P$25") (pinfunction "PE7_P$25") (pintype "bidirectional"))
    )
    (net (code "106") (name "unconnected-(U$1-PE8-PadP$26)") (class "Default")
      (node (ref "U$1") (pin "P$26") (pinfunction "PE8_P$26") (pintype "bidirectional"))
    )
    (net (code "107") (name "unconnected-(U$1-PE9-PadP$27)") (class "Default")
      (node (ref "U$1") (pin "P$27") (pinfunction "PE9_P$27") (pintype "bidirectional"))
    )
    (net (code "108") (name "unconnected-(U$1-PE10-PadP$28)") (class "Default")
      (node (ref "U$1") (pin "P$28") (pinfunction "PE10_P$28") (pintype "bidirectional"))
    )
    (net (code "109") (name "unconnected-(U$1-PE11-PadP$29)") (class "Default")
      (node (ref "U$1") (pin "P$29") (pinfunction "PE11_P$29") (pintype "bidirectional"))
    )
    (net (code "110") (name "unconnected-(U$1-PE12-PadP$30)") (class "Default")
      (node (ref "U$1") (pin "P$30") (pinfunction "PE12_P$30") (pintype "bidirectional"))
    )
    (net (code "111") (name "unconnected-(U$1-PE13-PadP$31)") (class "Default")
      (node (ref "U$1") (pin "P$31") (pinfunction "PE13_P$31") (pintype "bidirectional"))
    )
    (net (code "112") (name "unconnected-(U$1-PE14-PadP$32)") (class "Default")
      (node (ref "U$1") (pin "P$32") (pinfunction "PE14_P$32") (pintype "bidirectional"))
    )
    (net (code "113") (name "unconnected-(U$1-PE15-PadP$33)") (class "Default")
      (node (ref "U$1") (pin "P$33") (pinfunction "PE15_P$33") (pintype "bidirectional"))
    )
    (net (code "114") (name "unconnected-(U$1-PH0-PadP$57)") (class "Default")
      (node (ref "U$1") (pin "P$57") (pinfunction "PH0_P$57") (pintype "bidirectional"))
    )
    (net (code "115") (name "unconnected-(U$1-PH1-PadP$58)") (class "Default")
      (node (ref "U$1") (pin "P$58") (pinfunction "PH1_P$58") (pintype "bidirectional"))
    )
    (net (code "116") (name "unconnected-(U$1-VDD-PadP$3)") (class "Default")
      (node (ref "U$1") (pin "P$3") (pinfunction "VDD_P$3") (pintype "bidirectional"))
    )
    (net (code "117") (name "unconnected-(U$1-VDD1-PadP$4)") (class "Default")
      (node (ref "U$1") (pin "P$4") (pinfunction "VDD1_P$4") (pintype "bidirectional"))
    )
    (net (code "118") (name "unconnected-(U$1-VDD2-PadP$55)") (class "Default")
      (node (ref "U$1") (pin "P$55") (pinfunction "VDD2_P$55") (pintype "bidirectional"))
    )
    (net (code "119") (name "unconnected-(U$1-VDD3-PadP$56)") (class "Default")
      (node (ref "U$1") (pin "P$56") (pinfunction "VDD3_P$56") (pintype "bidirectional"))
    )
    (net (code "120") (name "unconnected-(U$1-VDD4-PadP$72)") (class "Default")
      (node (ref "U$1") (pin "P$72") (pinfunction "VDD4_P$72") (pintype "bidirectional"))
    )
    (net (code "121") (name "unconnected-(U$2A-CTL-PadP$3)") (class "Default")
      (node (ref "U$2") (pin "P$3") (pinfunction "CTL_P$3") (pintype "bidirectional"))
    )
    (net (code "122") (name "unconnected-(U$7A-CTL-PadP$3)") (class "Default")
      (node (ref "U$7") (pin "P$3") (pinfunction "CTL_P$3") (pintype "bidirectional"))
    )
    (net (code "123") (name "unconnected-(U$8A-CTL-PadP$3)") (class "Default")
      (node (ref "U$8") (pin "P$3") (pinfunction "CTL_P$3") (pintype "bidirectional"))
    )
    (net (code "124") (name "unconnected-(U$9A-CTL-PadP$3)") (class "Default")
      (node (ref "U$9") (pin "P$3") (pinfunction "CTL_P$3") (pintype "bidirectional"))
    )
    (net (code "125") (name "unconnected-(U$10A-CTL-PadP$3)") (class "Default")
      (node (ref "U$10") (pin "P$3") (pinfunction "CTL_P$3") (pintype "bidirectional"))
    )
    (net (code "126") (name "unconnected-(U$11A-CTL-PadP$3)") (class "Default")
      (node (ref "U$11") (pin "P$3") (pinfunction "CTL_P$3") (pintype "bidirectional"))
    )
    (net (code "127") (name "unconnected-(U$12A-CTL-PadP$3)") (class "Default")
      (node (ref "U$12") (pin "P$3") (pinfunction "CTL_P$3") (pintype "bidirectional"))
    )
    (net (code "128") (name "unconnected-(U$13A-CTL-PadP$3)") (class "Default")
      (node (ref "U$13") (pin "P$3") (pinfunction "CTL_P$3") (pintype "bidirectional"))
    )
    (net (code "129") (name "unconnected-(U3-CH1-PadP$3)") (class "Default")
      (node (ref "U3") (pin "P$3") (pinfunction "CH1_P$3") (pintype "bidirectional"))
    )
    (net (code "130") (name "unconnected-(U3-SO-PadP$8)") (class "Default")
      (node (ref "U3") (pin "P$8") (pinfunction "SO_P$8") (pintype "bidirectional"))
    )
  )
)
